# ESP32-Download-Motherboard.net
KiCad netlist of a schematic drawn in Altium Designer
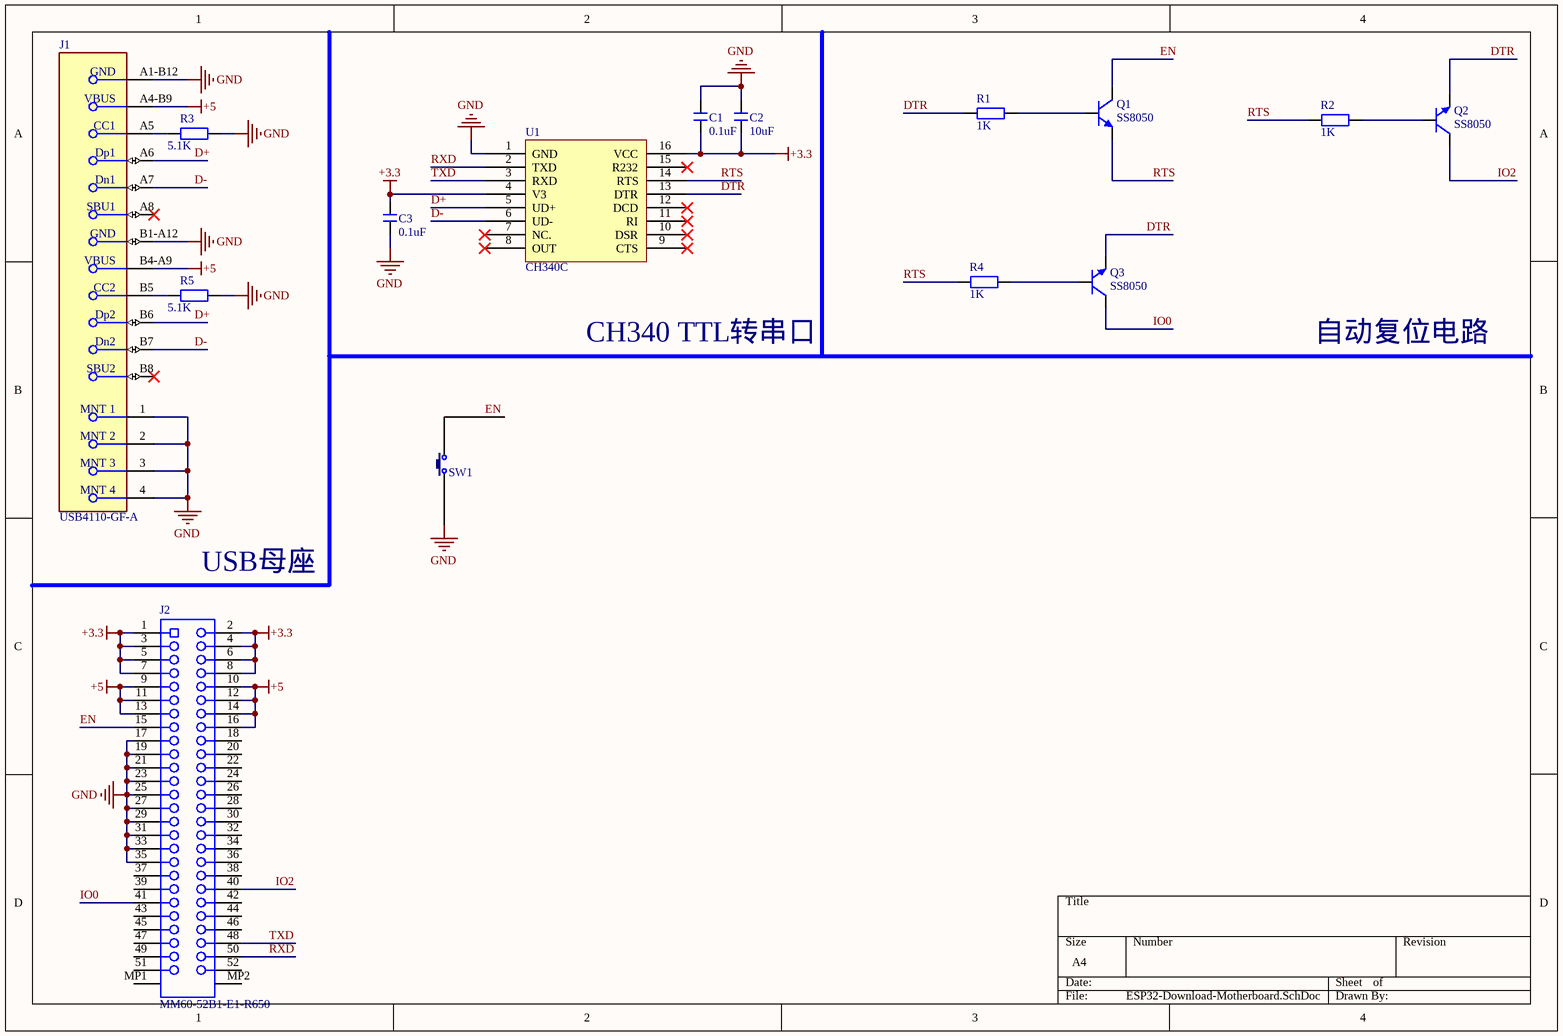
[diagram p0: ESP32-Download-Motherboard.SchDoc]

(export (version "E")
  (design (tool "Eeschema 10.0.6"))
  (components
    (comp (ref "C1")
      (value "0.1uF")
      (footprint "C 0603_L")
      (description "无极性贴片电容")
      (libsource (lib "电容-电阻-电感-电位器") (part "C"))
    )
    (comp (ref "C2")
      (value "10uF")
      (footprint "C 0603_L")
      (description "无极性贴片电容")
      (libsource (lib "电容-电阻-电感-电位器") (part "C"))
    )
    (comp (ref "C3")
      (value "0.1uF")
      (footprint "C 0603_L")
      (description "无极性贴片电容")
      (libsource (lib "电容-电阻-电感-电位器") (part "C"))
    )
    (comp (ref "J1")
      (value "USB4110-GF-A")
      (footprint "FP-USB4110-GF-A-MFG")
      (description "CONN USB 2.0 TYPE-C R/A SMT")
      (fields
        (field (name "OCTOPART") "https://octopart.com/usb4110-gf-a-gct-103941985")
        (field (name "MANUFACTURER") "GCT")
      )
      (libsource (lib "Altium Content Vault") (part "e23f2b38bb3c3f98e683ebab9ede730"))
    )
    (comp (ref "J2")
      (value "MM60-52B1-E1-R650")
      (footprint "MINI_PCIE_CONN_3130")
      (fields (field (name "MANUFACTURER") "JAE Electronics"))
      (libsource (lib "MINI_PCIE") (part "MINI_PCIE_CONN"))
    )
    (comp (ref "Q1")
      (value "SS8050")
      (footprint "SOT23-3N")
      (description "高频放大-NPN型")
      (libsource (lib "三极管") (part "8050-SMD"))
    )
    (comp (ref "Q2")
      (value "SS8050")
      (footprint "SOT23-3N")
      (description "高频放大-NPN型")
      (libsource (lib "三极管") (part "8050-SMD"))
    )
    (comp (ref "Q3")
      (value "SS8050")
      (footprint "SOT23-3N")
      (description "高频放大-NPN型")
      (libsource (lib "三极管") (part "8050-SMD"))
    )
    (comp (ref "R1")
      (value "1K")
      (footprint "R 0603_L")
      (description "贴片电阻")
      (libsource (lib "电容-电阻-电感-电位器") (part "R"))
    )
    (comp (ref "R2")
      (value "1K")
      (footprint "R 0603_L")
      (description "贴片电阻")
      (libsource (lib "电容-电阻-电感-电位器") (part "R"))
    )
    (comp (ref "R3")
      (value "5.1K")
      (footprint "R 0603_L")
      (description "贴片电阻")
      (libsource (lib "电容-电阻-电感-电位器") (part "R"))
    )
    (comp (ref "R4")
      (value "1K")
      (footprint "R 0603_L")
      (description "贴片电阻")
      (libsource (lib "电容-电阻-电感-电位器") (part "R"))
    )
    (comp (ref "R5")
      (value "5.1K")
      (footprint "R 0603_L")
      (description "贴片电阻")
      (libsource (lib "电容-电阻-电感-电位器") (part "R"))
    )
    (comp (ref "SW1")
      (value "3x6x5")
      (footprint "TSW SMD-3*6*2.5")
      (description "3x6轻触开关")
      (libsource (lib "按键-开关") (part "TSW 3x6"))
    )
    (comp (ref "U1") (value "CH340C") (footprint "SOP16N_N") (libsource (lib "Schlib1") (part "CH340C")))
  )
  (nets
    (net (code "1") (name "+3.3") (class "Default")
      (node (ref "C1") (pin "1") (pinfunction "1_1") (pintype "passive"))
      (node (ref "C2") (pin "1") (pinfunction "1_1") (pintype "passive"))
      (node (ref "C3") (pin "2") (pinfunction "2_2") (pintype "passive"))
      (node (ref "J2") (pin "1") (pinfunction "1_1") (pintype "passive"))
      (node (ref "J2") (pin "2") (pinfunction "2_2") (pintype "passive"))
      (node (ref "J2") (pin "3") (pinfunction "3_3") (pintype "passive"))
      (node (ref "J2") (pin "4") (pinfunction "4_4") (pintype "passive"))
      (node (ref "J2") (pin "5") (pinfunction "5_5") (pintype "passive"))
      (node (ref "J2") (pin "6") (pinfunction "6_6") (pintype "passive"))
      (node (ref "J2") (pin "7") (pinfunction "7_7") (pintype "passive"))
      (node (ref "J2") (pin "8") (pinfunction "8_8") (pintype "passive"))
      (node (ref "U1") (pin "16") (pinfunction "VCC_16") (pintype "passive"))
      (node (ref "U1") (pin "4") (pinfunction "V3_4") (pintype "passive"))
    )
    (net (code "2") (name "+5") (class "Default")
      (node (ref "J1") (pin "A4-B9") (pinfunction "VBUS_A4-B9") (pintype "power_in"))
      (node (ref "J1") (pin "B4-A9") (pinfunction "VBUS_B4-A9") (pintype "power_in"))
      (node (ref "J2") (pin "10") (pinfunction "10_10") (pintype "passive"))
      (node (ref "J2") (pin "11") (pinfunction "11_11") (pintype "passive"))
      (node (ref "J2") (pin "12") (pinfunction "12_12") (pintype "passive"))
      (node (ref "J2") (pin "13") (pinfunction "13_13") (pintype "passive"))
      (node (ref "J2") (pin "14") (pinfunction "14_14") (pintype "passive"))
      (node (ref "J2") (pin "16") (pinfunction "16_16") (pintype "passive"))
      (node (ref "J2") (pin "9") (pinfunction "9_9") (pintype "passive"))
    )
    (net (code "3") (name "/D+") (class "Default")
      (node (ref "J1") (pin "A6") (pinfunction "Dp1_A6") (pintype "bidirectional"))
      (node (ref "J1") (pin "B6") (pinfunction "Dp2_B6") (pintype "bidirectional"))
      (node (ref "U1") (pin "5") (pinfunction "UD+_5") (pintype "passive"))
    )
    (net (code "4") (name "/D-") (class "Default")
      (node (ref "J1") (pin "A7") (pinfunction "Dn1_A7") (pintype "bidirectional"))
      (node (ref "J1") (pin "B7") (pinfunction "Dn2_B7") (pintype "bidirectional"))
      (node (ref "U1") (pin "6") (pinfunction "UD-_6") (pintype "passive"))
    )
    (net (code "5") (name "/DTR") (class "Default")
      (node (ref "Q2") (pin "2") (pinfunction "E_2") (pintype "passive"))
      (node (ref "Q3") (pin "2") (pinfunction "E_2") (pintype "passive"))
      (node (ref "R1") (pin "1") (pinfunction "1_1") (pintype "passive"))
      (node (ref "U1") (pin "13") (pinfunction "DTR_13") (pintype "passive"))
    )
    (net (code "6") (name "/EN") (class "Default")
      (node (ref "J2") (pin "15") (pinfunction "15_15") (pintype "passive"))
      (node (ref "Q1") (pin "3") (pinfunction "C_3") (pintype "passive"))
      (node (ref "SW1") (pin "2") (pinfunction "2_2") (pintype "passive"))
    )
    (net (code "7") (name "/IO0") (class "Default")
      (node (ref "J2") (pin "41") (pinfunction "41_41") (pintype "passive"))
      (node (ref "Q3") (pin "3") (pinfunction "C_3") (pintype "passive"))
    )
    (net (code "8") (name "/IO2") (class "Default")
      (node (ref "J2") (pin "40") (pinfunction "40_40") (pintype "passive"))
      (node (ref "Q2") (pin "3") (pinfunction "C_3") (pintype "passive"))
    )
    (net (code "9") (name "/RTS") (class "Default")
      (node (ref "Q1") (pin "2") (pinfunction "E_2") (pintype "passive"))
      (node (ref "R2") (pin "1") (pinfunction "1_1") (pintype "passive"))
      (node (ref "R4") (pin "1") (pinfunction "1_1") (pintype "passive"))
      (node (ref "U1") (pin "14") (pinfunction "RTS_14") (pintype "passive"))
    )
    (net (code "10") (name "/RXD") (class "Default")
      (node (ref "J2") (pin "50") (pinfunction "50_50") (pintype "passive"))
      (node (ref "U1") (pin "2") (pinfunction "TXD_2") (pintype "passive"))
    )
    (net (code "11") (name "/TXD") (class "Default")
      (node (ref "J2") (pin "48") (pinfunction "48_48") (pintype "passive"))
      (node (ref "U1") (pin "3") (pinfunction "RXD_3") (pintype "passive"))
    )
    (net (code "12") (name "GND") (class "Default")
      (node (ref "C1") (pin "2") (pinfunction "2_2") (pintype "passive"))
      (node (ref "C2") (pin "2") (pinfunction "2_2") (pintype "passive"))
      (node (ref "C3") (pin "1") (pinfunction "1_1") (pintype "passive"))
      (node (ref "J1") (pin "1") (pinfunction "MNT_1_1") (pintype "passive"))
      (node (ref "J1") (pin "2") (pinfunction "MNT_2_2") (pintype "passive"))
      (node (ref "J1") (pin "3") (pinfunction "MNT_3_3") (pintype "passive"))
      (node (ref "J1") (pin "4") (pinfunction "MNT_4_4") (pintype "passive"))
      (node (ref "J1") (pin "A1-B12") (pinfunction "GND_A1-B12") (pintype "passive"))
      (node (ref "J1") (pin "B1-A12") (pinfunction "GND_B1-A12") (pintype "bidirectional"))
      (node (ref "J2") (pin "17") (pinfunction "17_17") (pintype "passive"))
      (node (ref "J2") (pin "19") (pinfunction "19_19") (pintype "passive"))
      (node (ref "J2") (pin "21") (pinfunction "21_21") (pintype "passive"))
      (node (ref "J2") (pin "23") (pinfunction "23_23") (pintype "passive"))
      (node (ref "J2") (pin "25") (pinfunction "25_25") (pintype "passive"))
      (node (ref "J2") (pin "27") (pinfunction "27_27") (pintype "passive"))
      (node (ref "J2") (pin "29") (pinfunction "29_29") (pintype "passive"))
      (node (ref "J2") (pin "31") (pinfunction "31_31") (pintype "passive"))
      (node (ref "J2") (pin "33") (pinfunction "33_33") (pintype "passive"))
      (node (ref "J2") (pin "35") (pinfunction "35_35") (pintype "passive"))
      (node (ref "R3") (pin "2") (pinfunction "2_2") (pintype "passive"))
      (node (ref "R5") (pin "2") (pinfunction "2_2") (pintype "passive"))
      (node (ref "SW1") (pin "1") (pinfunction "1_1") (pintype "passive"))
      (node (ref "U1") (pin "1") (pinfunction "GND_1") (pintype "passive"))
    )
    (net (code "13") (name "Net-(J1-CC1)") (class "Default")
      (node (ref "J1") (pin "A5") (pinfunction "CC1_A5") (pintype "power_in"))
      (node (ref "R3") (pin "1") (pinfunction "1_1") (pintype "passive"))
    )
    (net (code "14") (name "Net-(J1-CC2)") (class "Default")
      (node (ref "J1") (pin "B5") (pinfunction "CC2_B5") (pintype "power_in"))
      (node (ref "R5") (pin "1") (pinfunction "1_1") (pintype "passive"))
    )
    (net (code "15") (name "Net-(Q1-B)") (class "Default")
      (node (ref "Q1") (pin "1") (pinfunction "B_1") (pintype "passive"))
      (node (ref "R1") (pin "2") (pinfunction "2_2") (pintype "passive"))
    )
    (net (code "16") (name "Net-(Q2-B)") (class "Default")
      (node (ref "Q2") (pin "1") (pinfunction "B_1") (pintype "passive"))
      (node (ref "R2") (pin "2") (pinfunction "2_2") (pintype "passive"))
    )
    (net (code "17") (name "Net-(Q3-B)") (class "Default")
      (node (ref "Q3") (pin "1") (pinfunction "B_1") (pintype "passive"))
      (node (ref "R4") (pin "2") (pinfunction "2_2") (pintype "passive"))
    )
    (net (code "18") (name "unconnected-(J1-SBU1-PadA8)") (class "Default")
      (node (ref "J1") (pin "A8") (pinfunction "SBU1_A8") (pintype "bidirectional+no_connect"))
    )
    (net (code "19") (name "unconnected-(J1-SBU2-PadB8)") (class "Default")
      (node (ref "J1") (pin "B8") (pinfunction "SBU2_B8") (pintype "bidirectional+no_connect"))
    )
    (net (code "20") (name "unconnected-(J2-Pad18)") (class "Default")
      (node (ref "J2") (pin "18") (pinfunction "18_18") (pintype "passive"))
    )
    (net (code "21") (name "unconnected-(J2-Pad20)") (class "Default")
      (node (ref "J2") (pin "20") (pinfunction "20_20") (pintype "passive"))
    )
    (net (code "22") (name "unconnected-(J2-Pad22)") (class "Default")
      (node (ref "J2") (pin "22") (pinfunction "22_22") (pintype "passive"))
    )
    (net (code "23") (name "unconnected-(J2-Pad24)") (class "Default")
      (node (ref "J2") (pin "24") (pinfunction "24_24") (pintype "passive"))
    )
    (net (code "24") (name "unconnected-(J2-Pad26)") (class "Default")
      (node (ref "J2") (pin "26") (pinfunction "26_26") (pintype "passive"))
    )
    (net (code "25") (name "unconnected-(J2-Pad28)") (class "Default")
      (node (ref "J2") (pin "28") (pinfunction "28_28") (pintype "passive"))
    )
    (net (code "26") (name "unconnected-(J2-Pad30)") (class "Default")
      (node (ref "J2") (pin "30") (pinfunction "30_30") (pintype "passive"))
    )
    (net (code "27") (name "unconnected-(J2-Pad32)") (class "Default")
      (node (ref "J2") (pin "32") (pinfunction "32_32") (pintype "passive"))
    )
    (net (code "28") (name "unconnected-(J2-Pad34)") (class "Default")
      (node (ref "J2") (pin "34") (pinfunction "34_34") (pintype "passive"))
    )
    (net (code "29") (name "unconnected-(J2-Pad36)") (class "Default")
      (node (ref "J2") (pin "36") (pinfunction "36_36") (pintype "passive"))
    )
    (net (code "30") (name "unconnected-(J2-Pad37)") (class "Default")
      (node (ref "J2") (pin "37") (pinfunction "37_37") (pintype "passive"))
    )
    (net (code "31") (name "unconnected-(J2-Pad38)") (class "Default")
      (node (ref "J2") (pin "38") (pinfunction "38_38") (pintype "passive"))
    )
    (net (code "32") (name "unconnected-(J2-Pad39)") (class "Default")
      (node (ref "J2") (pin "39") (pinfunction "39_39") (pintype "passive"))
    )
    (net (code "33") (name "unconnected-(J2-Pad42)") (class "Default")
      (node (ref "J2") (pin "42") (pinfunction "42_42") (pintype "passive"))
    )
    (net (code "34") (name "unconnected-(J2-Pad43)") (class "Default")
      (node (ref "J2") (pin "43") (pinfunction "43_43") (pintype "passive"))
    )
    (net (code "35") (name "unconnected-(J2-Pad44)") (class "Default")
      (node (ref "J2") (pin "44") (pinfunction "44_44") (pintype "passive"))
    )
    (net (code "36") (name "unconnected-(J2-Pad45)") (class "Default")
      (node (ref "J2") (pin "45") (pinfunction "45_45") (pintype "passive"))
    )
    (net (code "37") (name "unconnected-(J2-Pad46)") (class "Default")
      (node (ref "J2") (pin "46") (pinfunction "46_46") (pintype "passive"))
    )
    (net (code "38") (name "unconnected-(J2-Pad47)") (class "Default")
      (node (ref "J2") (pin "47") (pinfunction "47_47") (pintype "passive"))
    )
    (net (code "39") (name "unconnected-(J2-Pad49)") (class "Default")
      (node (ref "J2") (pin "49") (pinfunction "49_49") (pintype "passive"))
    )
    (net (code "40") (name "unconnected-(J2-Pad51)") (class "Default")
      (node (ref "J2") (pin "51") (pinfunction "51_51") (pintype "passive"))
    )
    (net (code "41") (name "unconnected-(J2-Pad52)") (class "Default")
      (node (ref "J2") (pin "52") (pinfunction "52_52") (pintype "passive"))
    )
    (net (code "42") (name "unconnected-(J2-PadMP1)") (class "Default")
      (node (ref "J2") (pin "MP1") (pinfunction "MP1_MP1") (pintype "passive"))
    )
    (net (code "43") (name "unconnected-(J2-PadMP2)") (class "Default")
      (node (ref "J2") (pin "MP2") (pinfunction "MP2_MP2") (pintype "passive"))
    )
    (net (code "44") (name "unconnected-(U1-CTS-Pad9)") (class "Default")
      (node (ref "U1") (pin "9") (pinfunction "CTS_9") (pintype "passive+no_connect"))
    )
    (net (code "45") (name "unconnected-(U1-DCD-Pad12)") (class "Default")
      (node (ref "U1") (pin "12") (pinfunction "DCD_12") (pintype "passive+no_connect"))
    )
    (net (code "46") (name "unconnected-(U1-DSR-Pad10)") (class "Default")
      (node (ref "U1") (pin "10") (pinfunction "DSR_10") (pintype "passive+no_connect"))
    )
    (net (code "47") (name "unconnected-(U1-NC.-Pad7)") (class "Default")
      (node (ref "U1") (pin "7") (pinfunction "NC._7") (pintype "passive+no_connect"))
    )
    (net (code "48") (name "unconnected-(U1-OUT-Pad8)") (class "Default")
      (node (ref "U1") (pin "8") (pinfunction "OUT_8") (pintype "passive+no_connect"))
    )
    (net (code "49") (name "unconnected-(U1-R232-Pad15)") (class "Default")
      (node (ref "U1") (pin "15") (pinfunction "R232_15") (pintype "passive+no_connect"))
    )
    (net (code "50") (name "unconnected-(U1-RI-Pad11)") (class "Default")
      (node (ref "U1") (pin "11") (pinfunction "RI_11") (pintype "passive+no_connect"))
    )
  )
)
